# BMSv2.net
KiCad netlist of a schematic drawn in EAGLE
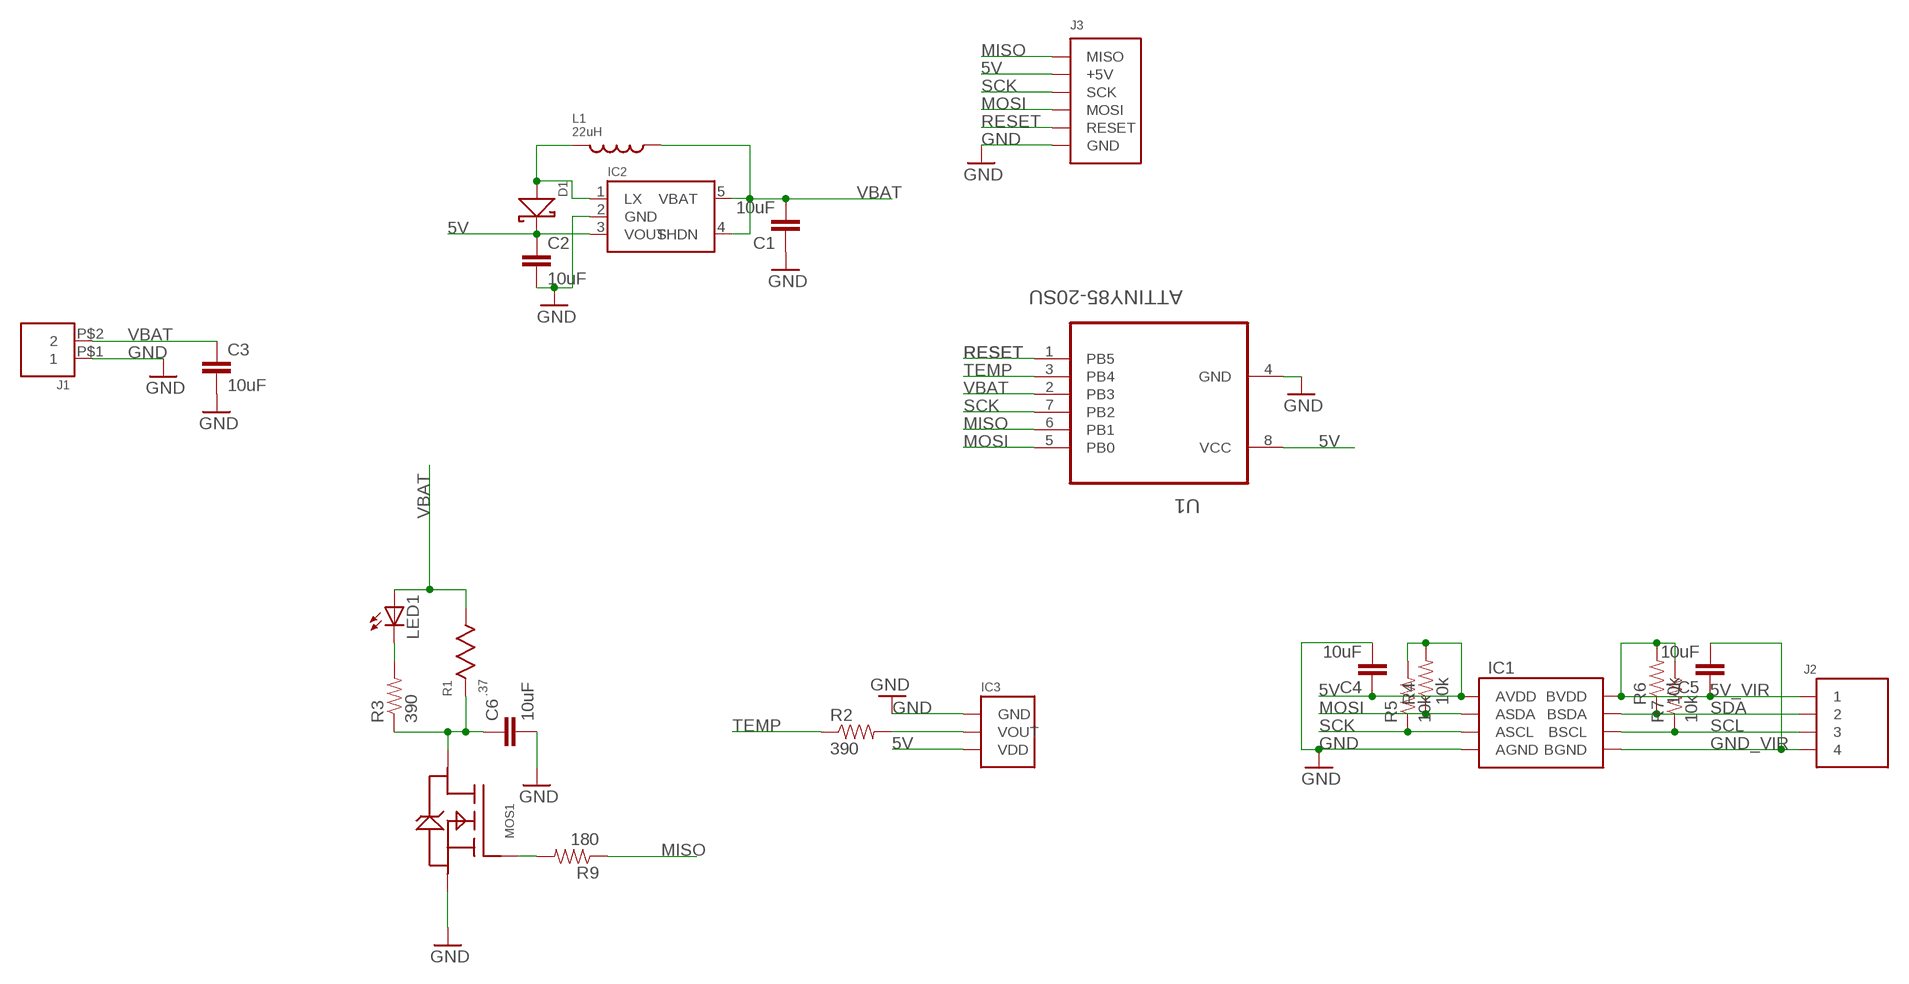
[diagram p0: schematic, sheet 1]

(export (version "E")
  (design (tool "Eeschema 10.0.6"))
  (components
    (comp (ref "C1")
      (value "10uF")
      (footprint "eagle-import:0805-CAP")
      (libsource (lib "eagle-import") (part "10UF10V10%(0805)"))
    )
    (comp (ref "C2")
      (value "10uF")
      (footprint "eagle-import:0805-CAP")
      (libsource (lib "eagle-import") (part "10UF10V10%(0805)"))
    )
    (comp (ref "C3")
      (value "10uF")
      (footprint "eagle-import:0805-CAP")
      (libsource (lib "eagle-import") (part "10UF10V10%(0805)"))
    )
    (comp (ref "C4")
      (value "10uF")
      (footprint "eagle-import:0805-CAP")
      (libsource (lib "eagle-import") (part "10UF10V10%(0805)"))
    )
    (comp (ref "C5")
      (value "10uF")
      (footprint "eagle-import:0805-CAP")
      (libsource (lib "eagle-import") (part "10UF10V10%(0805)"))
    )
    (comp (ref "C6")
      (value "10uF")
      (footprint "eagle-import:0805-CAP")
      (libsource (lib "eagle-import") (part "10UF10V10%(0805)"))
    )
    (comp (ref "D1")
      (value "DIODE_SCHOTTKYSOD-123")
      (footprint "eagle-import:SOD-123")
      (libsource (lib "eagle-import") (part "DIODE_SCHOTTKYSOD-123"))
    )
    (comp (ref "IC1")
      (value "SI8600_DUALCHANNELISO")
      (footprint "eagle-import:SOIC-8")
      (libsource (lib "eagle-import") (part "SI8600_DUALCHANNELISO"))
    )
    (comp (ref "IC2")
      (value "SP6641")
      (footprint "eagle-import:SOT-23")
      (libsource (lib "eagle-import") (part "SP6641"))
    )
    (comp (ref "IC3")
      (value "TEMP_MCP9701")
      (footprint "eagle-import:SOT-23-3")
      (libsource (lib "eagle-import") (part "TEMP_MCP9701"))
    )
    (comp (ref "J1")
      (value "CONNECTOR_2PIN")
      (footprint "eagle-import:2PIN_.1'")
      (libsource (lib "eagle-import") (part "CONNECTOR_2PIN"))
    )
    (comp (ref "J2")
      (value "CONNECTOR_4PIN")
      (footprint "eagle-import:4PIN_.1'")
      (libsource (lib "eagle-import") (part "CONNECTOR_4PIN"))
    )
    (comp (ref "J3")
      (value "ISPHEADER")
      (footprint "eagle-import:2X3PIN_.1'")
      (libsource (lib "eagle-import") (part "ISPHEADER"))
    )
    (comp (ref "L1")
      (value "22uH")
      (footprint "eagle-import:6X6MM_IND")
      (libsource (lib "eagle-import") (part "CHIP_IND1"))
    )
    (comp (ref "LED1")
      (value "LEDCHIPLED_0805")
      (footprint "eagle-import:CHIPLED_0805")
      (libsource (lib "eagle-import") (part "LEDCHIPLED_0805"))
    )
    (comp (ref "MOS1")
      (value "MOS_N_LOGIC_PSMN7R0")
      (footprint "eagle-import:LFPAK")
      (libsource (lib "eagle-import") (part "MOS_N_LOGIC_PSMN7R0"))
    )
    (comp (ref "R1")
      (value ".37")
      (footprint "eagle-import:TO-220-2")
      (libsource (lib "eagle-import") (part "RES_THROUGH"))
    )
    (comp (ref "R2")
      (value "390")
      (footprint "eagle-import:0805")
      (libsource (lib "eagle-import") (part "0.3OHM-1/8W-1%(0805)"))
    )
    (comp (ref "R3")
      (value "390")
      (footprint "eagle-import:0805")
      (libsource (lib "eagle-import") (part "0.3OHM-1/8W-1%(0805)"))
    )
    (comp (ref "R4")
      (value "10k")
      (footprint "eagle-import:0805")
      (libsource (lib "eagle-import") (part "0.3OHM-1/8W-1%(0805)"))
    )
    (comp (ref "R5")
      (value "10k")
      (footprint "eagle-import:0805")
      (libsource (lib "eagle-import") (part "0.3OHM-1/8W-1%(0805)"))
    )
    (comp (ref "R6")
      (value "10k")
      (footprint "eagle-import:0805")
      (libsource (lib "eagle-import") (part "0.3OHM-1/8W-1%(0805)"))
    )
    (comp (ref "R7")
      (value "10k")
      (footprint "eagle-import:0805")
      (libsource (lib "eagle-import") (part "0.3OHM-1/8W-1%(0805)"))
    )
    (comp (ref "R9")
      (value "180")
      (footprint "eagle-import:0805")
      (libsource (lib "eagle-import") (part "0.3OHM-1/8W-1%(0805)"))
    )
    (comp (ref "U1")
      (value "ATTINY85-20SU")
      (footprint "eagle-import:SOIC127P798X216-8N")
      (libsource (lib "eagle-import") (part "ATTINY85-20SU"))
    )
  )
  (nets
    (net (code "1") (name "/5V") (class "Default")
      (node (ref "C2") (pin "1") (pinfunction "1_1") (pintype "passive"))
      (node (ref "C4") (pin "1") (pinfunction "1_1") (pintype "passive"))
      (node (ref "D1") (pin "CATHODE") (pinfunction "CATHODE_CATHODE") (pintype "bidirectional"))
      (node (ref "IC1") (pin "P$1") (pinfunction "AVDD_P$1") (pintype "bidirectional"))
      (node (ref "IC2") (pin "3") (pinfunction "VOUT_3") (pintype "bidirectional"))
      (node (ref "IC3") (pin "1") (pinfunction "VDD_1") (pintype "bidirectional"))
      (node (ref "J3") (pin "P$2") (pinfunction "+5V_P$2") (pintype "bidirectional"))
      (node (ref "R4") (pin "2") (pinfunction "2_2") (pintype "passive"))
      (node (ref "R5") (pin "2") (pinfunction "2_2") (pintype "passive"))
      (node (ref "U1") (pin "8") (pinfunction "VCC_8") (pintype "power_in"))
    )
    (net (code "2") (name "/5V_VIR") (class "Default")
      (node (ref "C5") (pin "1") (pinfunction "1_1") (pintype "passive"))
      (node (ref "IC1") (pin "P$8") (pinfunction "BVDD_P$8") (pintype "bidirectional"))
      (node (ref "J2") (pin "P$1") (pinfunction "1_P$1") (pintype "bidirectional"))
      (node (ref "R6") (pin "2") (pinfunction "2_2") (pintype "passive"))
      (node (ref "R7") (pin "2") (pinfunction "2_2") (pintype "passive"))
    )
    (net (code "3") (name "/GND_VIR") (class "Default")
      (node (ref "C5") (pin "2") (pinfunction "2_2") (pintype "passive"))
      (node (ref "IC1") (pin "P$5") (pinfunction "BGND_P$5") (pintype "bidirectional"))
      (node (ref "J2") (pin "P$4") (pinfunction "4_P$4") (pintype "bidirectional"))
    )
    (net (code "4") (name "/MISO") (class "Default")
      (node (ref "J3") (pin "P$1") (pinfunction "MISO_P$1") (pintype "bidirectional"))
      (node (ref "R9") (pin "1") (pinfunction "1_1") (pintype "passive"))
      (node (ref "U1") (pin "6") (pinfunction "PB1_6") (pintype "bidirectional"))
    )
    (net (code "5") (name "/MOSI") (class "Default")
      (node (ref "IC1") (pin "P$2") (pinfunction "ASDA_P$2") (pintype "bidirectional"))
      (node (ref "J3") (pin "P$4") (pinfunction "MOSI_P$4") (pintype "bidirectional"))
      (node (ref "R4") (pin "1") (pinfunction "1_1") (pintype "passive"))
      (node (ref "U1") (pin "5") (pinfunction "PB0_5") (pintype "bidirectional"))
    )
    (net (code "6") (name "/RESET") (class "Default")
      (node (ref "J3") (pin "P$5") (pinfunction "RESET_P$5") (pintype "bidirectional"))
      (node (ref "U1") (pin "1") (pinfunction "PB5_1") (pintype "bidirectional"))
    )
    (net (code "7") (name "/SCK") (class "Default")
      (node (ref "IC1") (pin "P$3") (pinfunction "ASCL_P$3") (pintype "bidirectional"))
      (node (ref "J3") (pin "P$3") (pinfunction "SCK_P$3") (pintype "bidirectional"))
      (node (ref "R5") (pin "1") (pinfunction "1_1") (pintype "passive"))
      (node (ref "U1") (pin "7") (pinfunction "PB2_7") (pintype "bidirectional"))
    )
    (net (code "8") (name "/SCL") (class "Default")
      (node (ref "IC1") (pin "P$6") (pinfunction "BSCL_P$6") (pintype "bidirectional"))
      (node (ref "J2") (pin "P$3") (pinfunction "3_P$3") (pintype "bidirectional"))
      (node (ref "R7") (pin "1") (pinfunction "1_1") (pintype "passive"))
    )
    (net (code "9") (name "/SDA") (class "Default")
      (node (ref "IC1") (pin "P$7") (pinfunction "BSDA_P$7") (pintype "bidirectional"))
      (node (ref "J2") (pin "P$2") (pinfunction "2_P$2") (pintype "bidirectional"))
      (node (ref "R6") (pin "1") (pinfunction "1_1") (pintype "passive"))
    )
    (net (code "10") (name "/TEMP") (class "Default")
      (node (ref "R2") (pin "1") (pinfunction "1_1") (pintype "passive"))
      (node (ref "U1") (pin "3") (pinfunction "PB4_3") (pintype "bidirectional"))
    )
    (net (code "11") (name "/VBAT") (class "Default")
      (node (ref "C1") (pin "2") (pinfunction "2_2") (pintype "passive"))
      (node (ref "C3") (pin "1") (pinfunction "1_1") (pintype "passive"))
      (node (ref "IC2") (pin "4") (pinfunction "SHDN_4") (pintype "bidirectional"))
      (node (ref "IC2") (pin "5") (pinfunction "VBAT_5") (pintype "bidirectional"))
      (node (ref "J1") (pin "P$2") (pinfunction "2_P$2") (pintype "bidirectional"))
      (node (ref "L1") (pin "P$2") (pinfunction "P$2_P$2") (pintype "bidirectional"))
      (node (ref "LED1") (pin "A") (pinfunction "A_A") (pintype "passive"))
      (node (ref "R1") (pin "P$2") (pinfunction "P$2_P$2") (pintype "bidirectional"))
      (node (ref "U1") (pin "2") (pinfunction "PB3_2") (pintype "bidirectional"))
    )
    (net (code "12") (name "GND") (class "Default")
      (node (ref "C1") (pin "1") (pinfunction "1_1") (pintype "passive"))
      (node (ref "C2") (pin "2") (pinfunction "2_2") (pintype "passive"))
      (node (ref "C3") (pin "2") (pinfunction "2_2") (pintype "passive"))
      (node (ref "C4") (pin "2") (pinfunction "2_2") (pintype "passive"))
      (node (ref "C6") (pin "2") (pinfunction "2_2") (pintype "passive"))
      (node (ref "IC1") (pin "P$4") (pinfunction "AGND_P$4") (pintype "bidirectional"))
      (node (ref "IC2") (pin "2") (pinfunction "GND_2") (pintype "bidirectional"))
      (node (ref "IC3") (pin "3") (pinfunction "GND_3") (pintype "bidirectional"))
      (node (ref "J1") (pin "P$1") (pinfunction "1_P$1") (pintype "bidirectional"))
      (node (ref "J3") (pin "P$6") (pinfunction "GND_P$6") (pintype "bidirectional"))
      (node (ref "MOS1") (pin "P$1") (pinfunction "SOURCE_P$1") (pintype "bidirectional"))
      (node (ref "MOS1") (pin "P$2") (pinfunction "SOURCE_P$2") (pintype "bidirectional"))
      (node (ref "MOS1") (pin "P$3") (pinfunction "SOURCE_P$3") (pintype "bidirectional"))
      (node (ref "U1") (pin "4") (pinfunction "GND_4") (pintype "passive"))
    )
    (net (code "13") (name "Net-(IC2-LX)") (class "Default")
      (node (ref "D1") (pin "ANODE") (pinfunction "ANODE_ANODE") (pintype "bidirectional"))
      (node (ref "IC2") (pin "1") (pinfunction "LX_1") (pintype "bidirectional"))
      (node (ref "L1") (pin "P$1") (pinfunction "P$1_P$1") (pintype "bidirectional"))
    )
    (net (code "14") (name "Net-(IC3-VOUT)") (class "Default")
      (node (ref "IC3") (pin "2") (pinfunction "VOUT_2") (pintype "bidirectional"))
      (node (ref "R2") (pin "2") (pinfunction "2_2") (pintype "passive"))
    )
    (net (code "15") (name "Net-(LED1-PadC)") (class "Default")
      (node (ref "LED1") (pin "C") (pinfunction "C_C") (pintype "passive"))
      (node (ref "R3") (pin "2") (pinfunction "2_2") (pintype "passive"))
    )
    (net (code "16") (name "Net-(MOS1-DRAIN)") (class "Default")
      (node (ref "C6") (pin "1") (pinfunction "1_1") (pintype "passive"))
      (node (ref "MOS1") (pin "P$5") (pinfunction "DRAIN_P$5") (pintype "bidirectional"))
      (node (ref "R1") (pin "P$1") (pinfunction "P$1_P$1") (pintype "bidirectional"))
      (node (ref "R3") (pin "1") (pinfunction "1_1") (pintype "passive"))
    )
    (net (code "17") (name "Net-(MOS1-GATE)") (class "Default")
      (node (ref "MOS1") (pin "P$4") (pinfunction "GATE_P$4") (pintype "bidirectional"))
      (node (ref "R9") (pin "2") (pinfunction "2_2") (pintype "passive"))
    )
  )
)
